# CAN_Module.net
KiCad netlist of a schematic drawn in Altium Designer
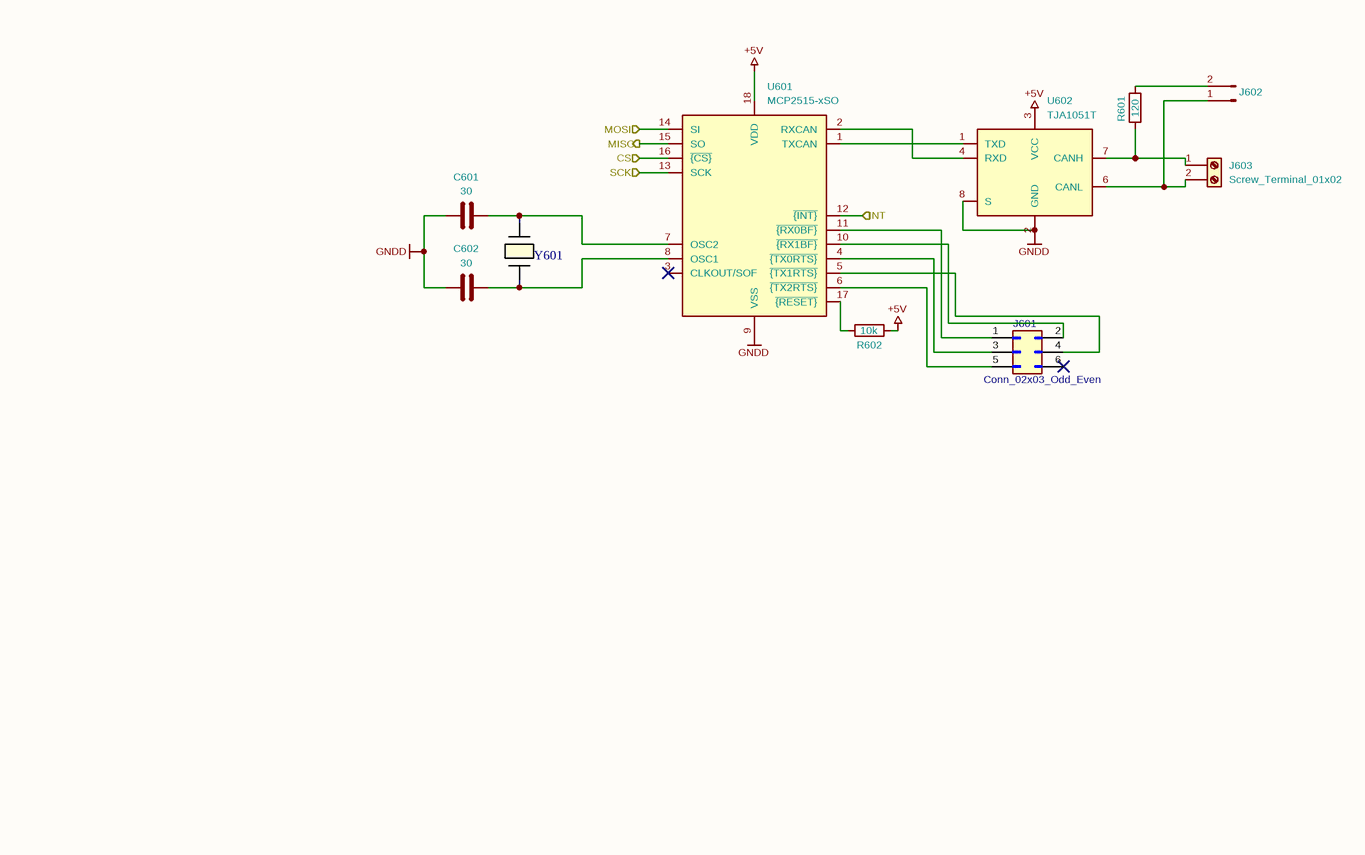
[diagram p0: CAN_Module.SchDoc]

(export (version "E")
  (design (tool "Eeschema 10.0.6"))
  (components
    (comp (ref "C601")
      (value "30")
      (footprint "C_0402_1005Metric_Pad0.74x0.62mm_HandSolder")
      (libsource (lib "Device") (part "C"))
    )
    (comp (ref "C602")
      (value "30")
      (footprint "C_0402_1005Metric_Pad0.74x0.62mm_HandSolder")
      (libsource (lib "Device") (part "C"))
    )
    (comp (ref "J601")
      (value "Conn_02x03_Odd_Even")
      (footprint "PinHeader_2x03_P2.54mm_Vertical")
      (libsource (lib "Connector_Generic") (part "Conn_02x03_Odd_Even"))
    )
    (comp (ref "J602")
      (value "Conn_01x02_Pin")
      (footprint "PinHeader_1x02_P2.54mm_Vertical")
      (libsource (lib "Connector") (part "Conn_01x02_Pin"))
    )
    (comp (ref "J603")
      (value "Screw_Terminal_01x02")
      (footprint "TerminalBlock_Xinya_XY308-2.54-2P_1x02_P2.54mm_Horizontal")
      (libsource (lib "Connector") (part "Screw_Terminal_01x02"))
    )
    (comp (ref "R601")
      (value "120")
      (footprint "R_0603_1608Metric_Pad0.98x0.95mm_HandSolder")
      (libsource (lib "Device") (part "R"))
    )
    (comp (ref "R602")
      (value "10k")
      (footprint "R_0603_1608Metric_Pad0.98x0.95mm_HandSolder")
      (libsource (lib "") (part "R_1"))
    )
    (comp (ref "U601")
      (value "MCP2515-xSO")
      (footprint "SOIC-SO18_M")
      (libsource (lib "Interface_CAN_LIN") (part "MCP2515-xSO"))
    )
    (comp (ref "U602")
      (value "TJA1051T")
      (footprint "NXP-SOIC-8_M")
      (libsource (lib "Interface_CAN_LIN") (part "TJA1051T"))
    )
    (comp (ref "Y601")
      (value "X49SM8MSD2SC")
      (footprint "H32_RAM")
      (libsource (lib "HC49US-10P244MHZ-16PF-30-EXT-SMD-H32-TR") (part "HC49US-10.244MHZ-16PF-30-EXT-SMD-H32-TR"))
    )
  )
  (nets
    (net (code "1") (name "+5V") (class "Default")
      (node (ref "R602") (pin "2") (pinfunction "2_2") (pintype "passive"))
      (node (ref "U601") (pin "18") (pinfunction "VDD_18") (pintype "passive"))
      (node (ref "U602") (pin "3") (pinfunction "VCC_3") (pintype "passive"))
    )
    (net (code "2") (name "/CS") (class "Default")
      (node (ref "U601") (pin "16") (pinfunction "~{{CS}}_16") (pintype "passive"))
    )
    (net (code "3") (name "/INT") (class "Default")
      (node (ref "U601") (pin "12") (pinfunction "~{{INT}}_12") (pintype "passive"))
    )
    (net (code "4") (name "/MISO") (class "Default")
      (node (ref "U601") (pin "15") (pinfunction "SO_15") (pintype "passive"))
    )
    (net (code "5") (name "/MOSI") (class "Default")
      (node (ref "U601") (pin "14") (pinfunction "SI_14") (pintype "passive"))
    )
    (net (code "6") (name "/SCK") (class "Default")
      (node (ref "U601") (pin "13") (pinfunction "SCK_13") (pintype "passive"))
    )
    (net (code "7") (name "GNDD") (class "Default")
      (node (ref "C601") (pin "1") (pinfunction "1_1") (pintype "passive"))
      (node (ref "C602") (pin "1") (pinfunction "1_1") (pintype "passive"))
      (node (ref "U601") (pin "9") (pinfunction "VSS_9") (pintype "passive"))
      (node (ref "U602") (pin "2") (pinfunction "GND_2") (pintype "passive"))
      (node (ref "U602") (pin "8") (pinfunction "S_8") (pintype "passive"))
    )
    (net (code "8") (name "Net-(J601-Pin_1)") (class "Default")
      (node (ref "J601") (pin "1") (pinfunction "Pin_1_1") (pintype "passive"))
      (node (ref "U601") (pin "11") (pinfunction "~{{RX0BF}}_11") (pintype "passive"))
    )
    (net (code "9") (name "Net-(J601-Pin_2)") (class "Default")
      (node (ref "J601") (pin "2") (pinfunction "Pin_2_2") (pintype "passive"))
      (node (ref "U601") (pin "10") (pinfunction "~{{RX1BF}}_10") (pintype "passive"))
    )
    (net (code "10") (name "Net-(J601-Pin_3)") (class "Default")
      (node (ref "J601") (pin "3") (pinfunction "Pin_3_3") (pintype "passive"))
      (node (ref "U601") (pin "4") (pinfunction "~{{TX0RTS}}_4") (pintype "passive"))
    )
    (net (code "11") (name "Net-(J601-Pin_4)") (class "Default")
      (node (ref "J601") (pin "4") (pinfunction "Pin_4_4") (pintype "passive"))
      (node (ref "U601") (pin "5") (pinfunction "~{{TX1RTS}}_5") (pintype "passive"))
    )
    (net (code "12") (name "Net-(J601-Pin_5)") (class "Default")
      (node (ref "J601") (pin "5") (pinfunction "Pin_5_5") (pintype "passive"))
      (node (ref "U601") (pin "6") (pinfunction "~{{TX2RTS}}_6") (pintype "passive"))
    )
    (net (code "13") (name "Net-(J602-Pin_1)") (class "Default")
      (node (ref "J602") (pin "1") (pinfunction "Pin_1_1") (pintype "passive"))
      (node (ref "J603") (pin "2") (pinfunction "Pin_2_2") (pintype "passive"))
      (node (ref "U602") (pin "6") (pinfunction "CANL_6") (pintype "passive"))
    )
    (net (code "14") (name "Net-(J602-Pin_2)") (class "Default")
      (node (ref "J602") (pin "2") (pinfunction "Pin_2_2") (pintype "passive"))
      (node (ref "R601") (pin "1") (pinfunction "1_1") (pintype "passive"))
    )
    (net (code "15") (name "Net-(J603-Pin_1)") (class "Default")
      (node (ref "J603") (pin "1") (pinfunction "Pin_1_1") (pintype "passive"))
      (node (ref "R601") (pin "2") (pinfunction "2_2") (pintype "passive"))
      (node (ref "U602") (pin "7") (pinfunction "CANH_7") (pintype "passive"))
    )
    (net (code "16") (name "Net-(U601-OSC1)") (class "Default")
      (node (ref "C602") (pin "2") (pinfunction "2_2") (pintype "passive"))
      (node (ref "U601") (pin "8") (pinfunction "OSC1_8") (pintype "passive"))
      (node (ref "Y601") (pin "2") (pinfunction "2_2") (pintype "passive"))
    )
    (net (code "17") (name "Net-(U601-OSC2)") (class "Default")
      (node (ref "C601") (pin "2") (pinfunction "2_2") (pintype "passive"))
      (node (ref "U601") (pin "7") (pinfunction "OSC2_7") (pintype "passive"))
      (node (ref "Y601") (pin "1") (pinfunction "1_1") (pintype "passive"))
    )
    (net (code "18") (name "Net-(U601-RXCAN)") (class "Default")
      (node (ref "U601") (pin "2") (pinfunction "RXCAN_2") (pintype "passive"))
      (node (ref "U602") (pin "4") (pinfunction "RXD_4") (pintype "passive"))
    )
    (net (code "19") (name "Net-(U601-TXCAN)") (class "Default")
      (node (ref "U601") (pin "1") (pinfunction "TXCAN_1") (pintype "passive"))
      (node (ref "U602") (pin "1") (pinfunction "TXD_1") (pintype "passive"))
    )
    (net (code "20") (name "Net-(U601-~{{RESET}})") (class "Default")
      (node (ref "R602") (pin "1") (pinfunction "1_1") (pintype "passive"))
      (node (ref "U601") (pin "17") (pinfunction "~{{RESET}}_17") (pintype "passive"))
    )
    (net (code "21") (name "unconnected-(J601-Pin_6-Pad6)") (class "Default")
      (node (ref "J601") (pin "6") (pinfunction "Pin_6_6") (pintype "passive+no_connect"))
    )
    (net (code "22") (name "unconnected-(U601-CLKOUT{slash}SOF-Pad3)") (class "Default")
      (node (ref "U601") (pin "3") (pinfunction "CLKOUT/SOF_3") (pintype "passive+no_connect"))
    )
    (net (code "23") (name "unconnected-(U602-NC-Pad5)") (class "Default")
      (node (ref "U602") (pin "5") (pinfunction "NC_5") (pintype "passive"))
    )
  )
)
